# isp.net
KiCad netlist of a schematic drawn in EAGLE
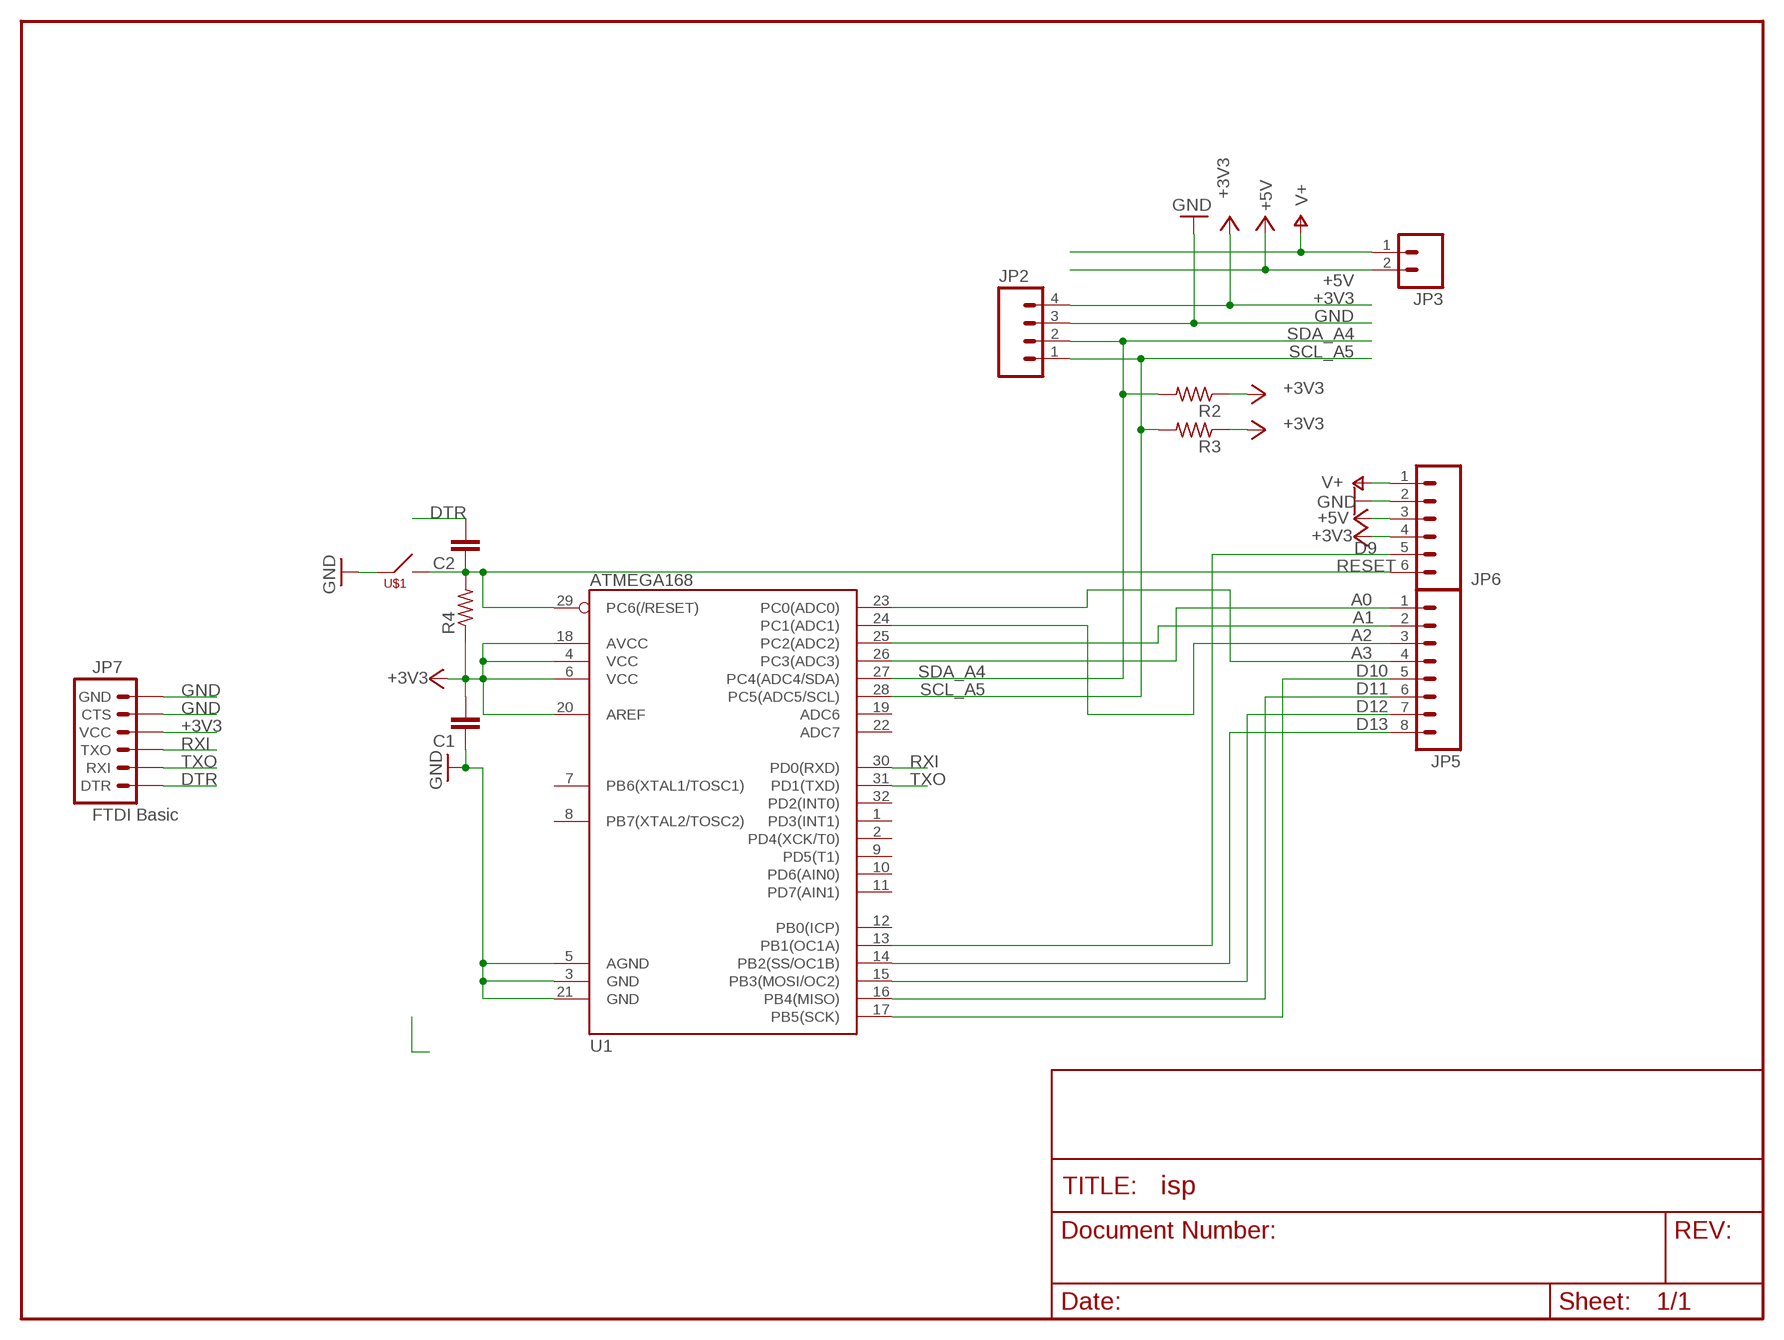
[diagram p0: schematic, sheet 1]

(export (version "E")
  (design (tool "Eeschema 10.0.6"))
  (components
    (comp (ref "C1")
      (value "CAPKIT")
      (footprint "eagle-import:CAP-PTH-SMALL-KIT")
      (libsource (lib "eagle-import") (part "CAPKIT"))
    )
    (comp (ref "C2")
      (value "CAPKIT")
      (footprint "eagle-import:CAP-PTH-SMALL-KIT")
      (libsource (lib "eagle-import") (part "CAPKIT"))
    )
    (comp (ref "JP2")
      (value "M04PTH")
      (footprint "eagle-import:1X04")
      (libsource (lib "eagle-import") (part "M04PTH"))
    )
    (comp (ref "JP3")
      (value "M02PTH")
      (footprint "eagle-import:1X02")
      (libsource (lib "eagle-import") (part "M02PTH"))
    )
    (comp (ref "JP5")
      (value "M081X08")
      (footprint "eagle-import:1X08")
      (libsource (lib "eagle-import") (part "M081X08"))
    )
    (comp (ref "JP6")
      (value "M06SIP")
      (footprint "eagle-import:1X06")
      (libsource (lib "eagle-import") (part "M06SIP"))
    )
    (comp (ref "JP7")
      (value "FTDI Basic")
      (footprint "eagle-import:1X06")
      (libsource (lib "eagle-import") (part "ARDUINO_SERIAL_PROGRAMPTH"))
    )
    (comp (ref "R2")
      (value "R-US_0204/2V")
      (footprint "eagle-import:0204V")
      (libsource (lib "eagle-import") (part "R-US_0204/2V"))
    )
    (comp (ref "R3")
      (value "R-US_0204/2V")
      (footprint "eagle-import:0204V")
      (libsource (lib "eagle-import") (part "R-US_0204/2V"))
    )
    (comp (ref "R4")
      (value "R-US_0204/2V")
      (footprint "eagle-import:0204V")
      (libsource (lib "eagle-import") (part "R-US_0204/2V"))
    )
    (comp (ref "U$1")
      (value "PTS635_SWITCH")
      (footprint "eagle-import:PTS635_SWITCH")
      (libsource (lib "eagle-import") (part "PTS635_SWITCH"))
    )
    (comp (ref "U1")
      (value "ATMEGA168")
      (footprint "eagle-import:TQFP32-08")
      (libsource (lib "eagle-import") (part "ATMEGA168"))
    )
  )
  (nets
    (net (code "1") (name "+3V3") (class "Default")
      (node (ref "C1") (pin "2") (pinfunction "2_2") (pintype "passive"))
      (node (ref "JP2") (pin "4") (pinfunction "4_4") (pintype "passive"))
      (node (ref "JP6") (pin "4") (pinfunction "4_4") (pintype "passive"))
      (node (ref "JP7") (pin "4") (pinfunction "VCC_4") (pintype "passive"))
      (node (ref "R2") (pin "1") (pinfunction "1_1") (pintype "passive"))
      (node (ref "R3") (pin "1") (pinfunction "1_1") (pintype "passive"))
      (node (ref "R4") (pin "1") (pinfunction "1_1") (pintype "passive"))
      (node (ref "U1") (pin "18") (pinfunction "AVCC_18") (pintype "bidirectional"))
      (node (ref "U1") (pin "20") (pinfunction "AREF_20") (pintype "bidirectional"))
      (node (ref "U1") (pin "4") (pinfunction "VCC_4") (pintype "bidirectional"))
      (node (ref "U1") (pin "6") (pinfunction "VCC_6") (pintype "bidirectional"))
    )
    (net (code "2") (name "+5V") (class "Default")
      (node (ref "JP3") (pin "2") (pinfunction "2_2") (pintype "passive"))
      (node (ref "JP6") (pin "3") (pinfunction "3_3") (pintype "passive"))
    )
    (net (code "3") (name "/A0") (class "Default")
      (node (ref "JP5") (pin "4") (pinfunction "4_4") (pintype "passive"))
      (node (ref "U1") (pin "23") (pinfunction "PC0(ADC0)_23") (pintype "bidirectional"))
    )
    (net (code "4") (name "/A1") (class "Default")
      (node (ref "JP5") (pin "3") (pinfunction "3_3") (pintype "passive"))
      (node (ref "U1") (pin "24") (pinfunction "PC1(ADC1)_24") (pintype "bidirectional"))
    )
    (net (code "5") (name "/A2") (class "Default")
      (node (ref "JP5") (pin "2") (pinfunction "2_2") (pintype "passive"))
      (node (ref "U1") (pin "25") (pinfunction "PC2(ADC2)_25") (pintype "bidirectional"))
    )
    (net (code "6") (name "/A3") (class "Default")
      (node (ref "JP5") (pin "1") (pinfunction "1_1") (pintype "passive"))
      (node (ref "U1") (pin "26") (pinfunction "PC3(ADC3)_26") (pintype "bidirectional"))
    )
    (net (code "7") (name "/D9") (class "Default")
      (node (ref "JP6") (pin "5") (pinfunction "5_5") (pintype "passive"))
      (node (ref "U1") (pin "13") (pinfunction "PB1(OC1A)_13") (pintype "bidirectional"))
    )
    (net (code "8") (name "/D10") (class "Default")
      (node (ref "JP5") (pin "8") (pinfunction "8_8") (pintype "passive"))
      (node (ref "U1") (pin "14") (pinfunction "PB2(SS/OC1B)_14") (pintype "bidirectional"))
    )
    (net (code "9") (name "/D11") (class "Default")
      (node (ref "JP5") (pin "7") (pinfunction "7_7") (pintype "passive"))
      (node (ref "U1") (pin "15") (pinfunction "PB3(MOSI/OC2)_15") (pintype "bidirectional"))
    )
    (net (code "10") (name "/D12") (class "Default")
      (node (ref "JP5") (pin "6") (pinfunction "6_6") (pintype "passive"))
      (node (ref "U1") (pin "16") (pinfunction "PB4(MISO)_16") (pintype "bidirectional"))
    )
    (net (code "11") (name "/D13") (class "Default")
      (node (ref "JP5") (pin "5") (pinfunction "5_5") (pintype "passive"))
      (node (ref "U1") (pin "17") (pinfunction "PB5(SCK)_17") (pintype "bidirectional"))
    )
    (net (code "12") (name "/DTR") (class "Default")
      (node (ref "C2") (pin "2") (pinfunction "2_2") (pintype "passive"))
      (node (ref "JP7") (pin "1") (pinfunction "DTR_1") (pintype "passive"))
    )
    (net (code "13") (name "/RESET") (class "Default")
      (node (ref "C2") (pin "1") (pinfunction "1_1") (pintype "passive"))
      (node (ref "JP6") (pin "6") (pinfunction "6_6") (pintype "passive"))
      (node (ref "R4") (pin "2") (pinfunction "2_2") (pintype "passive"))
      (node (ref "U$1") (pin "P$2") (pinfunction "P$2_P$2") (pintype "bidirectional"))
      (node (ref "U1") (pin "29") (pinfunction "PC6(/RESET)_29") (pintype "bidirectional"))
    )
    (net (code "14") (name "/RXI") (class "Default")
      (node (ref "JP7") (pin "3") (pinfunction "TXO_3") (pintype "passive"))
      (node (ref "U1") (pin "30") (pinfunction "PD0(RXD)_30") (pintype "bidirectional"))
    )
    (net (code "15") (name "/SCL_A5") (class "Default")
      (node (ref "JP2") (pin "1") (pinfunction "1_1") (pintype "passive"))
      (node (ref "R3") (pin "2") (pinfunction "2_2") (pintype "passive"))
      (node (ref "U1") (pin "28") (pinfunction "PC5(ADC5/SCL)_28") (pintype "bidirectional"))
    )
    (net (code "16") (name "/SDA_A4") (class "Default")
      (node (ref "JP2") (pin "2") (pinfunction "2_2") (pintype "passive"))
      (node (ref "R2") (pin "2") (pinfunction "2_2") (pintype "passive"))
      (node (ref "U1") (pin "27") (pinfunction "PC4(ADC4/SDA)_27") (pintype "bidirectional"))
    )
    (net (code "17") (name "/TXO") (class "Default")
      (node (ref "JP7") (pin "2") (pinfunction "RXI_2") (pintype "passive"))
      (node (ref "U1") (pin "31") (pinfunction "PD1(TXD)_31") (pintype "bidirectional"))
    )
    (net (code "18") (name "GND") (class "Default")
      (node (ref "C1") (pin "1") (pinfunction "1_1") (pintype "passive"))
      (node (ref "JP2") (pin "3") (pinfunction "3_3") (pintype "passive"))
      (node (ref "JP6") (pin "2") (pinfunction "2_2") (pintype "passive"))
      (node (ref "JP7") (pin "5") (pinfunction "CTS_5") (pintype "passive"))
      (node (ref "JP7") (pin "6") (pinfunction "GND_6") (pintype "passive"))
      (node (ref "U$1") (pin "P$1") (pinfunction "P$1_P$1") (pintype "bidirectional"))
      (node (ref "U1") (pin "21") (pinfunction "GND_21") (pintype "bidirectional"))
      (node (ref "U1") (pin "3") (pinfunction "GND_3") (pintype "bidirectional"))
      (node (ref "U1") (pin "5") (pinfunction "AGND_5") (pintype "bidirectional"))
    )
    (net (code "19") (name "V+") (class "Default")
      (node (ref "JP3") (pin "1") (pinfunction "1_1") (pintype "passive"))
      (node (ref "JP6") (pin "1") (pinfunction "1_1") (pintype "passive"))
    )
    (net (code "20") (name "unconnected-(U1-ADC6-Pad19)") (class "Default")
      (node (ref "U1") (pin "19") (pinfunction "ADC6_19") (pintype "bidirectional"))
    )
    (net (code "21") (name "unconnected-(U1-ADC7-Pad22)") (class "Default")
      (node (ref "U1") (pin "22") (pinfunction "ADC7_22") (pintype "bidirectional"))
    )
    (net (code "22") (name "unconnected-(U1-PB0(ICP)-Pad12)") (class "Default")
      (node (ref "U1") (pin "12") (pinfunction "PB0(ICP)_12") (pintype "bidirectional"))
    )
    (net (code "23") (name "unconnected-(U1-PB6(XTAL1{slash}TOSC1)-Pad7)") (class "Default")
      (node (ref "U1") (pin "7") (pinfunction "PB6(XTAL1/TOSC1)_7") (pintype "bidirectional"))
    )
    (net (code "24") (name "unconnected-(U1-PB7(XTAL2{slash}TOSC2)-Pad8)") (class "Default")
      (node (ref "U1") (pin "8") (pinfunction "PB7(XTAL2/TOSC2)_8") (pintype "bidirectional"))
    )
    (net (code "25") (name "unconnected-(U1-PD2(INT0)-Pad32)") (class "Default")
      (node (ref "U1") (pin "32") (pinfunction "PD2(INT0)_32") (pintype "bidirectional"))
    )
    (net (code "26") (name "unconnected-(U1-PD3(INT1)-Pad1)") (class "Default")
      (node (ref "U1") (pin "1") (pinfunction "PD3(INT1)_1") (pintype "bidirectional"))
    )
    (net (code "27") (name "unconnected-(U1-PD4(XCK{slash}T0)-Pad2)") (class "Default")
      (node (ref "U1") (pin "2") (pinfunction "PD4(XCK/T0)_2") (pintype "bidirectional"))
    )
    (net (code "28") (name "unconnected-(U1-PD5(T1)-Pad9)") (class "Default")
      (node (ref "U1") (pin "9") (pinfunction "PD5(T1)_9") (pintype "bidirectional"))
    )
    (net (code "29") (name "unconnected-(U1-PD6(AIN0)-Pad10)") (class "Default")
      (node (ref "U1") (pin "10") (pinfunction "PD6(AIN0)_10") (pintype "bidirectional"))
    )
    (net (code "30") (name "unconnected-(U1-PD7(AIN1)-Pad11)") (class "Default")
      (node (ref "U1") (pin "11") (pinfunction "PD7(AIN1)_11") (pintype "bidirectional"))
    )
  )
)
